# design.net
KiCad netlist of a schematic drawn in EAGLE
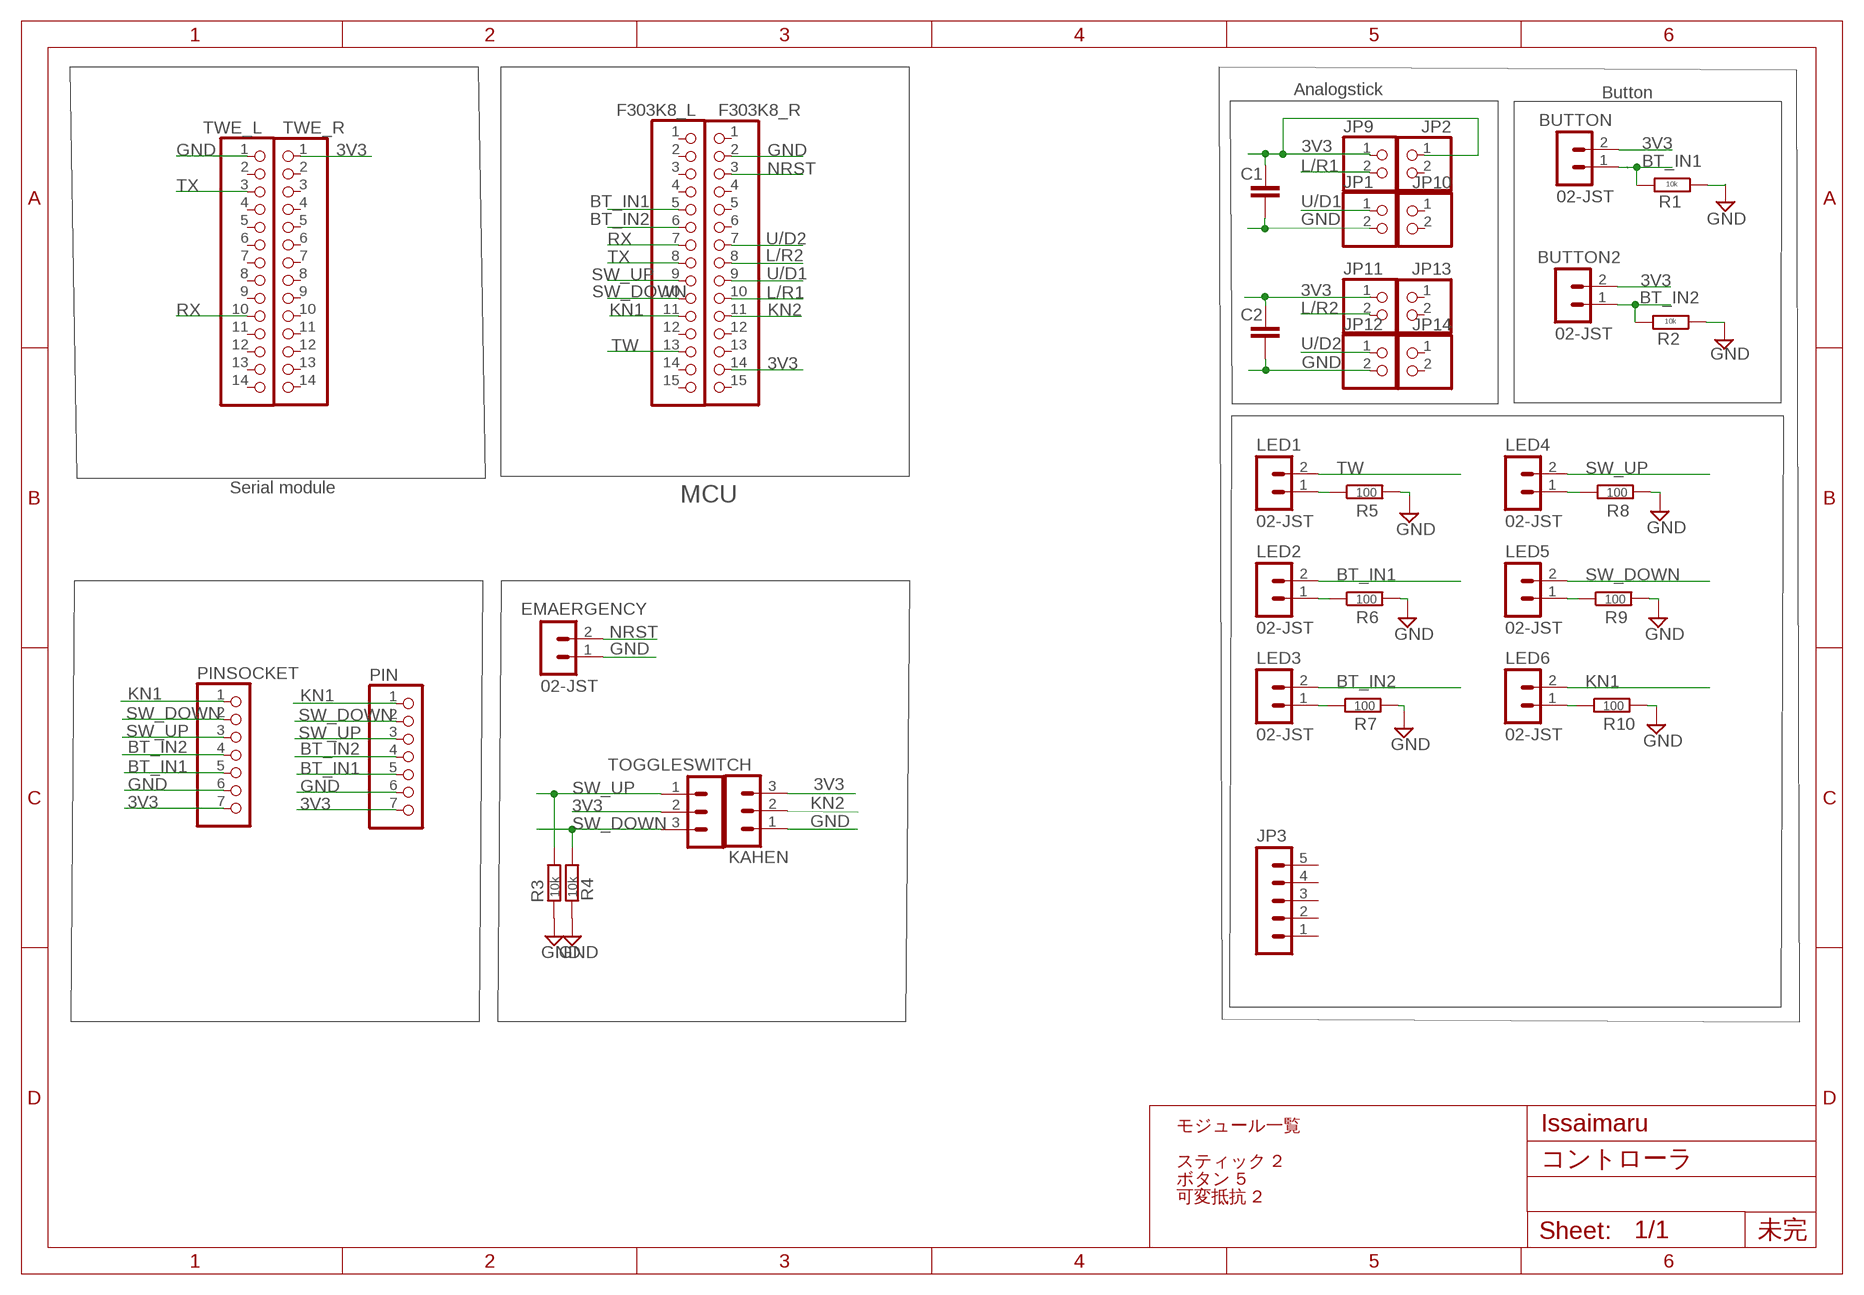
[diagram p0: schematic, sheet 1]

(export (version "E")
  (design (tool "Eeschema 10.0.6"))
  (components
    (comp (ref "BUTTON")
      (value "02-JST")
      (footprint "eagle-import:B2B-XH")
      (libsource (lib "eagle-import") (part "02-JST"))
    )
    (comp (ref "BUTTON2")
      (value "02-JST")
      (footprint "eagle-import:B2B-XH")
      (libsource (lib "eagle-import") (part "02-JST"))
    )
    (comp (ref "C1")
      (value "C-EU025-024X044")
      (footprint "eagle-import:C025-024X044")
      (libsource (lib "eagle-import") (part "C-EU025-024X044"))
    )
    (comp (ref "C2")
      (value "C-EU025-024X044")
      (footprint "eagle-import:C025-024X044")
      (libsource (lib "eagle-import") (part "C-EU025-024X044"))
    )
    (comp (ref "EMAERGENCY")
      (value "02-JST")
      (footprint "eagle-import:B2B-XH")
      (libsource (lib "eagle-import") (part "02-JST"))
    )
    (comp (ref "F303K8_L")
      (value "PINHD-1X15")
      (footprint "eagle-import:1X15")
      (libsource (lib "eagle-import") (part "PINHD-1X15"))
    )
    (comp (ref "F303K8_R")
      (value "PINHD-1X15")
      (footprint "eagle-import:1X15")
      (libsource (lib "eagle-import") (part "PINHD-1X15"))
    )
    (comp (ref "JP1")
      (value "PINHD-1X2")
      (footprint "eagle-import:1X02")
      (libsource (lib "eagle-import") (part "PINHD-1X2"))
    )
    (comp (ref "JP2")
      (value "PINHD-1X2")
      (footprint "eagle-import:1X02")
      (libsource (lib "eagle-import") (part "PINHD-1X2"))
    )
    (comp (ref "JP3")
      (value "05-JST")
      (footprint "eagle-import:B5B-XH")
      (libsource (lib "eagle-import") (part "05-JST"))
    )
    (comp (ref "JP9")
      (value "PINHD-1X2")
      (footprint "eagle-import:1X02")
      (libsource (lib "eagle-import") (part "PINHD-1X2"))
    )
    (comp (ref "JP10")
      (value "PINHD-1X2")
      (footprint "eagle-import:1X02")
      (libsource (lib "eagle-import") (part "PINHD-1X2"))
    )
    (comp (ref "JP11")
      (value "PINHD-1X2")
      (footprint "eagle-import:1X02")
      (libsource (lib "eagle-import") (part "PINHD-1X2"))
    )
    (comp (ref "JP12")
      (value "PINHD-1X2")
      (footprint "eagle-import:1X02")
      (libsource (lib "eagle-import") (part "PINHD-1X2"))
    )
    (comp (ref "JP13")
      (value "PINHD-1X2")
      (footprint "eagle-import:1X02")
      (libsource (lib "eagle-import") (part "PINHD-1X2"))
    )
    (comp (ref "JP14")
      (value "PINHD-1X2")
      (footprint "eagle-import:1X02")
      (libsource (lib "eagle-import") (part "PINHD-1X2"))
    )
    (comp (ref "KAHEN")
      (value "03-JST")
      (footprint "eagle-import:B3B-XH")
      (libsource (lib "eagle-import") (part "03-JST"))
    )
    (comp (ref "LED1")
      (value "02-JST")
      (footprint "eagle-import:B2B-XH")
      (libsource (lib "eagle-import") (part "con-jst-xh (1)_02-JST"))
    )
    (comp (ref "LED2")
      (value "02-JST")
      (footprint "eagle-import:B2B-XH")
      (libsource (lib "eagle-import") (part "con-jst-xh (1)_02-JST"))
    )
    (comp (ref "LED3")
      (value "02-JST")
      (footprint "eagle-import:B2B-XH")
      (libsource (lib "eagle-import") (part "con-jst-xh (1)_02-JST"))
    )
    (comp (ref "LED4")
      (value "02-JST")
      (footprint "eagle-import:B2B-XH")
      (libsource (lib "eagle-import") (part "con-jst-xh (1)_02-JST"))
    )
    (comp (ref "LED5")
      (value "02-JST")
      (footprint "eagle-import:B2B-XH")
      (libsource (lib "eagle-import") (part "con-jst-xh (1)_02-JST"))
    )
    (comp (ref "LED6")
      (value "02-JST")
      (footprint "eagle-import:B2B-XH")
      (libsource (lib "eagle-import") (part "con-jst-xh (1)_02-JST"))
    )
    (comp (ref "PIN")
      (value "PINHD-1X7")
      (footprint "eagle-import:1X07")
      (libsource (lib "eagle-import") (part "PINHD-1X7"))
    )
    (comp (ref "PINSOCKET")
      (value "PINHD-1X7")
      (footprint "eagle-import:1X07")
      (libsource (lib "eagle-import") (part "PINHD-1X7"))
    )
    (comp (ref "R1")
      (value "10k")
      (footprint "eagle-import:0204_7")
      (libsource (lib "eagle-import") (part "R-EU_0204/7"))
    )
    (comp (ref "R2")
      (value "10k")
      (footprint "eagle-import:0204_7")
      (libsource (lib "eagle-import") (part "R-EU_0204/7"))
    )
    (comp (ref "R3")
      (value "10k")
      (footprint "eagle-import:0204_7")
      (libsource (lib "eagle-import") (part "R-EU_0204/7"))
    )
    (comp (ref "R4")
      (value "10k")
      (footprint "eagle-import:0204_7")
      (libsource (lib "eagle-import") (part "R-EU_0204/7"))
    )
    (comp (ref "R5")
      (value "100")
      (footprint "eagle-import:0204_7")
      (libsource (lib "eagle-import") (part "R-EU_0204/7"))
    )
    (comp (ref "R6")
      (value "100")
      (footprint "eagle-import:0204_7")
      (libsource (lib "eagle-import") (part "R-EU_0204/7"))
    )
    (comp (ref "R7")
      (value "100")
      (footprint "eagle-import:0204_7")
      (libsource (lib "eagle-import") (part "R-EU_0204/7"))
    )
    (comp (ref "R8")
      (value "100")
      (footprint "eagle-import:0204_7")
      (libsource (lib "eagle-import") (part "R-EU_0204/7"))
    )
    (comp (ref "R9")
      (value "100")
      (footprint "eagle-import:0204_7")
      (libsource (lib "eagle-import") (part "R-EU_0204/7"))
    )
    (comp (ref "R10")
      (value "100")
      (footprint "eagle-import:0204_7")
      (libsource (lib "eagle-import") (part "R-EU_0204/7"))
    )
    (comp (ref "TOGGLESWITCH")
      (value "03-JST")
      (footprint "eagle-import:B3B-XH")
      (libsource (lib "eagle-import") (part "03-JST"))
    )
    (comp (ref "TWE_L")
      (value "PINHD-1X14")
      (footprint "eagle-import:1X14")
      (libsource (lib "eagle-import") (part "PINHD-1X14"))
    )
    (comp (ref "TWE_R")
      (value "PINHD-1X14")
      (footprint "eagle-import:1X14")
      (libsource (lib "eagle-import") (part "PINHD-1X14"))
    )
  )
  (nets
    (net (code "1") (name "/3V3") (class "Default")
      (node (ref "BUTTON") (pin "2") (pinfunction "2_2") (pintype "passive"))
      (node (ref "BUTTON2") (pin "2") (pinfunction "2_2") (pintype "passive"))
      (node (ref "C1") (pin "1") (pinfunction "1_1") (pintype "passive"))
      (node (ref "C2") (pin "1") (pinfunction "1_1") (pintype "passive"))
      (node (ref "F303K8_R") (pin "14") (pinfunction "14_14") (pintype "passive"))
      (node (ref "JP11") (pin "1") (pinfunction "1_1") (pintype "passive"))
      (node (ref "JP9") (pin "1") (pinfunction "1_1") (pintype "passive"))
      (node (ref "KAHEN") (pin "3") (pinfunction "3_3") (pintype "passive"))
      (node (ref "PIN") (pin "7") (pinfunction "7_7") (pintype "passive"))
      (node (ref "PINSOCKET") (pin "7") (pinfunction "7_7") (pintype "passive"))
      (node (ref "TOGGLESWITCH") (pin "2") (pinfunction "2_2") (pintype "passive"))
      (node (ref "TWE_R") (pin "1") (pinfunction "1_1") (pintype "passive"))
    )
    (net (code "2") (name "/BT_IN1") (class "Default")
      (node (ref "BUTTON") (pin "1") (pinfunction "1_1") (pintype "passive"))
      (node (ref "F303K8_L") (pin "5") (pinfunction "5_5") (pintype "passive"))
      (node (ref "LED2") (pin "2") (pinfunction "2_2") (pintype "passive"))
      (node (ref "PIN") (pin "5") (pinfunction "5_5") (pintype "passive"))
      (node (ref "PINSOCKET") (pin "5") (pinfunction "5_5") (pintype "passive"))
      (node (ref "R1") (pin "2") (pinfunction "2_2") (pintype "passive"))
    )
    (net (code "3") (name "/BT_IN2") (class "Default")
      (node (ref "BUTTON2") (pin "1") (pinfunction "1_1") (pintype "passive"))
      (node (ref "F303K8_L") (pin "6") (pinfunction "6_6") (pintype "passive"))
      (node (ref "LED3") (pin "2") (pinfunction "2_2") (pintype "passive"))
      (node (ref "PIN") (pin "4") (pinfunction "4_4") (pintype "passive"))
      (node (ref "PINSOCKET") (pin "4") (pinfunction "4_4") (pintype "passive"))
      (node (ref "R2") (pin "2") (pinfunction "2_2") (pintype "passive"))
    )
    (net (code "4") (name "/KN1") (class "Default")
      (node (ref "F303K8_L") (pin "11") (pinfunction "11_11") (pintype "passive"))
      (node (ref "LED6") (pin "2") (pinfunction "2_2") (pintype "passive"))
      (node (ref "PIN") (pin "1") (pinfunction "1_1") (pintype "passive"))
      (node (ref "PINSOCKET") (pin "1") (pinfunction "1_1") (pintype "passive"))
    )
    (net (code "5") (name "/KN2") (class "Default")
      (node (ref "F303K8_R") (pin "11") (pinfunction "11_11") (pintype "passive"))
      (node (ref "KAHEN") (pin "2") (pinfunction "2_2") (pintype "passive"))
    )
    (net (code "6") (name "/L{slash}R1") (class "Default")
      (node (ref "F303K8_R") (pin "10") (pinfunction "10_10") (pintype "passive"))
      (node (ref "JP9") (pin "2") (pinfunction "2_2") (pintype "passive"))
    )
    (net (code "7") (name "/L{slash}R2") (class "Default")
      (node (ref "F303K8_R") (pin "8") (pinfunction "8_8") (pintype "passive"))
      (node (ref "JP11") (pin "2") (pinfunction "2_2") (pintype "passive"))
    )
    (net (code "8") (name "/NRST") (class "Default")
      (node (ref "EMAERGENCY") (pin "2") (pinfunction "2_2") (pintype "passive"))
      (node (ref "F303K8_R") (pin "3") (pinfunction "3_3") (pintype "passive"))
    )
    (net (code "9") (name "/RX") (class "Default")
      (node (ref "F303K8_L") (pin "7") (pinfunction "7_7") (pintype "passive"))
      (node (ref "TWE_L") (pin "10") (pinfunction "10_10") (pintype "passive"))
    )
    (net (code "10") (name "/SW_DOWN") (class "Default")
      (node (ref "F303K8_L") (pin "10") (pinfunction "10_10") (pintype "passive"))
      (node (ref "LED5") (pin "2") (pinfunction "2_2") (pintype "passive"))
      (node (ref "PIN") (pin "2") (pinfunction "2_2") (pintype "passive"))
      (node (ref "PINSOCKET") (pin "2") (pinfunction "2_2") (pintype "passive"))
      (node (ref "R4") (pin "2") (pinfunction "2_2") (pintype "passive"))
      (node (ref "TOGGLESWITCH") (pin "3") (pinfunction "3_3") (pintype "passive"))
    )
    (net (code "11") (name "/SW_UP") (class "Default")
      (node (ref "F303K8_L") (pin "9") (pinfunction "9_9") (pintype "passive"))
      (node (ref "LED4") (pin "2") (pinfunction "2_2") (pintype "passive"))
      (node (ref "PIN") (pin "3") (pinfunction "3_3") (pintype "passive"))
      (node (ref "PINSOCKET") (pin "3") (pinfunction "3_3") (pintype "passive"))
      (node (ref "R3") (pin "2") (pinfunction "2_2") (pintype "passive"))
      (node (ref "TOGGLESWITCH") (pin "1") (pinfunction "1_1") (pintype "passive"))
    )
    (net (code "12") (name "/TW") (class "Default")
      (node (ref "F303K8_L") (pin "13") (pinfunction "13_13") (pintype "passive"))
      (node (ref "LED1") (pin "2") (pinfunction "2_2") (pintype "passive"))
    )
    (net (code "13") (name "/TX") (class "Default")
      (node (ref "F303K8_L") (pin "8") (pinfunction "8_8") (pintype "passive"))
      (node (ref "TWE_L") (pin "3") (pinfunction "3_3") (pintype "passive"))
    )
    (net (code "14") (name "/U{slash}D1") (class "Default")
      (node (ref "F303K8_R") (pin "9") (pinfunction "9_9") (pintype "passive"))
      (node (ref "JP1") (pin "1") (pinfunction "1_1") (pintype "passive"))
    )
    (net (code "15") (name "/U{slash}D2") (class "Default")
      (node (ref "F303K8_R") (pin "7") (pinfunction "7_7") (pintype "passive"))
      (node (ref "JP12") (pin "1") (pinfunction "1_1") (pintype "passive"))
    )
    (net (code "16") (name "GND") (class "Default")
      (node (ref "C1") (pin "2") (pinfunction "2_2") (pintype "passive"))
      (node (ref "C2") (pin "2") (pinfunction "2_2") (pintype "passive"))
      (node (ref "EMAERGENCY") (pin "1") (pinfunction "1_1") (pintype "passive"))
      (node (ref "F303K8_R") (pin "2") (pinfunction "2_2") (pintype "passive"))
      (node (ref "JP1") (pin "2") (pinfunction "2_2") (pintype "passive"))
      (node (ref "JP12") (pin "2") (pinfunction "2_2") (pintype "passive"))
      (node (ref "KAHEN") (pin "1") (pinfunction "1_1") (pintype "passive"))
      (node (ref "PIN") (pin "6") (pinfunction "6_6") (pintype "passive"))
      (node (ref "PINSOCKET") (pin "6") (pinfunction "6_6") (pintype "passive"))
      (node (ref "R1") (pin "1") (pinfunction "1_1") (pintype "passive"))
      (node (ref "R10") (pin "2") (pinfunction "2_2") (pintype "passive"))
      (node (ref "R2") (pin "1") (pinfunction "1_1") (pintype "passive"))
      (node (ref "R3") (pin "1") (pinfunction "1_1") (pintype "passive"))
      (node (ref "R4") (pin "1") (pinfunction "1_1") (pintype "passive"))
      (node (ref "R5") (pin "2") (pinfunction "2_2") (pintype "passive"))
      (node (ref "R6") (pin "2") (pinfunction "2_2") (pintype "passive"))
      (node (ref "R7") (pin "2") (pinfunction "2_2") (pintype "passive"))
      (node (ref "R8") (pin "2") (pinfunction "2_2") (pintype "passive"))
      (node (ref "R9") (pin "2") (pinfunction "2_2") (pintype "passive"))
      (node (ref "TWE_L") (pin "1") (pinfunction "1_1") (pintype "passive"))
    )
    (net (code "17") (name "Net-(LED1-Pad1)") (class "Default")
      (node (ref "LED1") (pin "1") (pinfunction "1_1") (pintype "passive"))
      (node (ref "R5") (pin "1") (pinfunction "1_1") (pintype "passive"))
    )
    (net (code "18") (name "Net-(LED2-Pad1)") (class "Default")
      (node (ref "LED2") (pin "1") (pinfunction "1_1") (pintype "passive"))
      (node (ref "R6") (pin "1") (pinfunction "1_1") (pintype "passive"))
    )
    (net (code "19") (name "Net-(LED3-Pad1)") (class "Default")
      (node (ref "LED3") (pin "1") (pinfunction "1_1") (pintype "passive"))
      (node (ref "R7") (pin "1") (pinfunction "1_1") (pintype "passive"))
    )
    (net (code "20") (name "Net-(LED4-Pad1)") (class "Default")
      (node (ref "LED4") (pin "1") (pinfunction "1_1") (pintype "passive"))
      (node (ref "R8") (pin "1") (pinfunction "1_1") (pintype "passive"))
    )
    (net (code "21") (name "Net-(LED5-Pad1)") (class "Default")
      (node (ref "LED5") (pin "1") (pinfunction "1_1") (pintype "passive"))
      (node (ref "R9") (pin "1") (pinfunction "1_1") (pintype "passive"))
    )
    (net (code "22") (name "Net-(LED6-Pad1)") (class "Default")
      (node (ref "LED6") (pin "1") (pinfunction "1_1") (pintype "passive"))
      (node (ref "R10") (pin "1") (pinfunction "1_1") (pintype "passive"))
    )
    (net (code "23") (name "unconnected-(F303K8_L-Pad1)") (class "Default")
      (node (ref "F303K8_L") (pin "1") (pinfunction "1_1") (pintype "passive"))
    )
    (net (code "24") (name "unconnected-(F303K8_L-Pad2)") (class "Default")
      (node (ref "F303K8_L") (pin "2") (pinfunction "2_2") (pintype "passive"))
    )
    (net (code "25") (name "unconnected-(F303K8_L-Pad3)") (class "Default")
      (node (ref "F303K8_L") (pin "3") (pinfunction "3_3") (pintype "passive"))
    )
    (net (code "26") (name "unconnected-(F303K8_L-Pad4)") (class "Default")
      (node (ref "F303K8_L") (pin "4") (pinfunction "4_4") (pintype "passive"))
    )
    (net (code "27") (name "unconnected-(F303K8_L-Pad12)") (class "Default")
      (node (ref "F303K8_L") (pin "12") (pinfunction "12_12") (pintype "passive"))
    )
    (net (code "28") (name "unconnected-(F303K8_L-Pad14)") (class "Default")
      (node (ref "F303K8_L") (pin "14") (pinfunction "14_14") (pintype "passive"))
    )
    (net (code "29") (name "unconnected-(F303K8_L-Pad15)") (class "Default")
      (node (ref "F303K8_L") (pin "15") (pinfunction "15_15") (pintype "passive"))
    )
    (net (code "30") (name "unconnected-(F303K8_R-Pad1)") (class "Default")
      (node (ref "F303K8_R") (pin "1") (pinfunction "1_1") (pintype "passive"))
    )
    (net (code "31") (name "unconnected-(F303K8_R-Pad4)") (class "Default")
      (node (ref "F303K8_R") (pin "4") (pinfunction "4_4") (pintype "passive"))
    )
    (net (code "32") (name "unconnected-(F303K8_R-Pad5)") (class "Default")
      (node (ref "F303K8_R") (pin "5") (pinfunction "5_5") (pintype "passive"))
    )
    (net (code "33") (name "unconnected-(F303K8_R-Pad6)") (class "Default")
      (node (ref "F303K8_R") (pin "6") (pinfunction "6_6") (pintype "passive"))
    )
    (net (code "34") (name "unconnected-(F303K8_R-Pad12)") (class "Default")
      (node (ref "F303K8_R") (pin "12") (pinfunction "12_12") (pintype "passive"))
    )
    (net (code "35") (name "unconnected-(F303K8_R-Pad13)") (class "Default")
      (node (ref "F303K8_R") (pin "13") (pinfunction "13_13") (pintype "passive"))
    )
    (net (code "36") (name "unconnected-(F303K8_R-Pad15)") (class "Default")
      (node (ref "F303K8_R") (pin "15") (pinfunction "15_15") (pintype "passive"))
    )
    (net (code "37") (name "unconnected-(JP2-Pad1)") (class "Default")
      (node (ref "JP2") (pin "1") (pinfunction "1_1") (pintype "passive"))
    )
    (net (code "38") (name "unconnected-(JP2-Pad2)") (class "Default")
      (node (ref "JP2") (pin "2") (pinfunction "2_2") (pintype "passive"))
    )
    (net (code "39") (name "unconnected-(JP3-Pad1)") (class "Default")
      (node (ref "JP3") (pin "1") (pinfunction "1_1") (pintype "passive"))
    )
    (net (code "40") (name "unconnected-(JP3-Pad2)") (class "Default")
      (node (ref "JP3") (pin "2") (pinfunction "2_2") (pintype "passive"))
    )
    (net (code "41") (name "unconnected-(JP3-Pad3)") (class "Default")
      (node (ref "JP3") (pin "3") (pinfunction "3_3") (pintype "passive"))
    )
    (net (code "42") (name "unconnected-(JP3-Pad4)") (class "Default")
      (node (ref "JP3") (pin "4") (pinfunction "4_4") (pintype "passive"))
    )
    (net (code "43") (name "unconnected-(JP3-Pad5)") (class "Default")
      (node (ref "JP3") (pin "5") (pinfunction "5_5") (pintype "passive"))
    )
    (net (code "44") (name "unconnected-(JP10-Pad1)") (class "Default")
      (node (ref "JP10") (pin "1") (pinfunction "1_1") (pintype "passive"))
    )
    (net (code "45") (name "unconnected-(JP10-Pad2)") (class "Default")
      (node (ref "JP10") (pin "2") (pinfunction "2_2") (pintype "passive"))
    )
    (net (code "46") (name "unconnected-(JP13-Pad1)") (class "Default")
      (node (ref "JP13") (pin "1") (pinfunction "1_1") (pintype "passive"))
    )
    (net (code "47") (name "unconnected-(JP13-Pad2)") (class "Default")
      (node (ref "JP13") (pin "2") (pinfunction "2_2") (pintype "passive"))
    )
    (net (code "48") (name "unconnected-(JP14-Pad1)") (class "Default")
      (node (ref "JP14") (pin "1") (pinfunction "1_1") (pintype "passive"))
    )
    (net (code "49") (name "unconnected-(JP14-Pad2)") (class "Default")
      (node (ref "JP14") (pin "2") (pinfunction "2_2") (pintype "passive"))
    )
    (net (code "50") (name "unconnected-(TWE_L-Pad2)") (class "Default")
      (node (ref "TWE_L") (pin "2") (pinfunction "2_2") (pintype "passive"))
    )
    (net (code "51") (name "unconnected-(TWE_L-Pad4)") (class "Default")
      (node (ref "TWE_L") (pin "4") (pinfunction "4_4") (pintype "passive"))
    )
    (net (code "52") (name "unconnected-(TWE_L-Pad5)") (class "Default")
      (node (ref "TWE_L") (pin "5") (pinfunction "5_5") (pintype "passive"))
    )
    (net (code "53") (name "unconnected-(TWE_L-Pad6)") (class "Default")
      (node (ref "TWE_L") (pin "6") (pinfunction "6_6") (pintype "passive"))
    )
    (net (code "54") (name "unconnected-(TWE_L-Pad7)") (class "Default")
      (node (ref "TWE_L") (pin "7") (pinfunction "7_7") (pintype "passive"))
    )
    (net (code "55") (name "unconnected-(TWE_L-Pad8)") (class "Default")
      (node (ref "TWE_L") (pin "8") (pinfunction "8_8") (pintype "passive"))
    )
    (net (code "56") (name "unconnected-(TWE_L-Pad9)") (class "Default")
      (node (ref "TWE_L") (pin "9") (pinfunction "9_9") (pintype "passive"))
    )
    (net (code "57") (name "unconnected-(TWE_L-Pad11)") (class "Default")
      (node (ref "TWE_L") (pin "11") (pinfunction "11_11") (pintype "passive"))
    )
    (net (code "58") (name "unconnected-(TWE_L-Pad12)") (class "Default")
      (node (ref "TWE_L") (pin "12") (pinfunction "12_12") (pintype "passive"))
    )
    (net (code "59") (name "unconnected-(TWE_L-Pad13)") (class "Default")
      (node (ref "TWE_L") (pin "13") (pinfunction "13_13") (pintype "passive"))
    )
    (net (code "60") (name "unconnected-(TWE_L-Pad14)") (class "Default")
      (node (ref "TWE_L") (pin "14") (pinfunction "14_14") (pintype "passive"))
    )
    (net (code "61") (name "unconnected-(TWE_R-Pad2)") (class "Default")
      (node (ref "TWE_R") (pin "2") (pinfunction "2_2") (pintype "passive"))
    )
    (net (code "62") (name "unconnected-(TWE_R-Pad3)") (class "Default")
      (node (ref "TWE_R") (pin "3") (pinfunction "3_3") (pintype "passive"))
    )
    (net (code "63") (name "unconnected-(TWE_R-Pad4)") (class "Default")
      (node (ref "TWE_R") (pin "4") (pinfunction "4_4") (pintype "passive"))
    )
    (net (code "64") (name "unconnected-(TWE_R-Pad5)") (class "Default")
      (node (ref "TWE_R") (pin "5") (pinfunction "5_5") (pintype "passive"))
    )
    (net (code "65") (name "unconnected-(TWE_R-Pad6)") (class "Default")
      (node (ref "TWE_R") (pin "6") (pinfunction "6_6") (pintype "passive"))
    )
    (net (code "66") (name "unconnected-(TWE_R-Pad7)") (class "Default")
      (node (ref "TWE_R") (pin "7") (pinfunction "7_7") (pintype "passive"))
    )
    (net (code "67") (name "unconnected-(TWE_R-Pad8)") (class "Default")
      (node (ref "TWE_R") (pin "8") (pinfunction "8_8") (pintype "passive"))
    )
    (net (code "68") (name "unconnected-(TWE_R-Pad9)") (class "Default")
      (node (ref "TWE_R") (pin "9") (pinfunction "9_9") (pintype "passive"))
    )
    (net (code "69") (name "unconnected-(TWE_R-Pad10)") (class "Default")
      (node (ref "TWE_R") (pin "10") (pinfunction "10_10") (pintype "passive"))
    )
    (net (code "70") (name "unconnected-(TWE_R-Pad11)") (class "Default")
      (node (ref "TWE_R") (pin "11") (pinfunction "11_11") (pintype "passive"))
    )
    (net (code "71") (name "unconnected-(TWE_R-Pad12)") (class "Default")
      (node (ref "TWE_R") (pin "12") (pinfunction "12_12") (pintype "passive"))
    )
    (net (code "72") (name "unconnected-(TWE_R-Pad13)") (class "Default")
      (node (ref "TWE_R") (pin "13") (pinfunction "13_13") (pintype "passive"))
    )
    (net (code "73") (name "unconnected-(TWE_R-Pad14)") (class "Default")
      (node (ref "TWE_R") (pin "14") (pinfunction "14_14") (pintype "passive"))
    )
  )
)
